# tunnelAmp.net
KiCad netlist of a schematic drawn in EAGLE
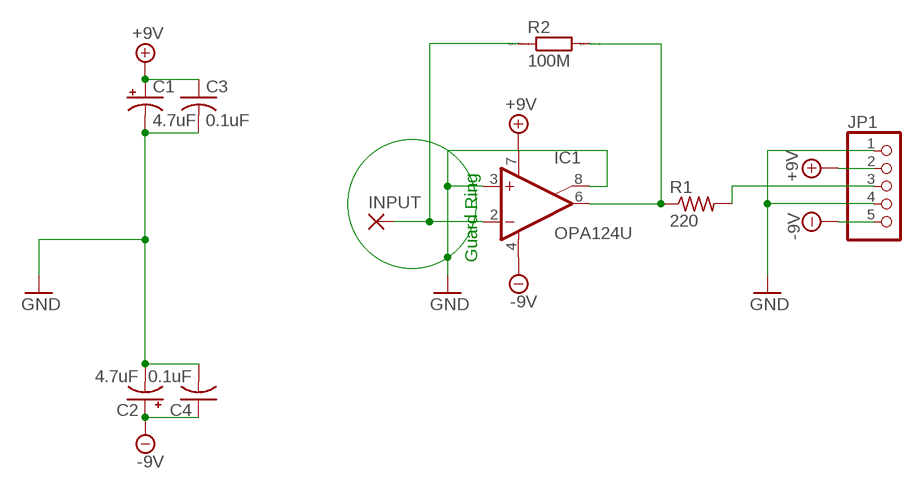
[diagram p0: schematic, sheet 1]

(export (version "E")
  (design (tool "Eeschema 10.0.6"))
  (components
    (comp (ref "C1")
      (value "4.7uF")
      (footprint "eagle-import:C_6032-28W")
      (libsource (lib "eagle-import") (part "CPOL-USC/6032-28W"))
    )
    (comp (ref "C2")
      (value "4.7uF")
      (footprint "eagle-import:C_6032-28W")
      (libsource (lib "eagle-import") (part "CPOL-USC/6032-28W"))
    )
    (comp (ref "C3")
      (value "0.1uF")
      (footprint "eagle-import:C0603")
      (libsource (lib "eagle-import") (part "C-USC0603"))
    )
    (comp (ref "C4")
      (value "0.1uF")
      (footprint "eagle-import:C0603")
      (libsource (lib "eagle-import") (part "C-USC0603"))
    )
    (comp (ref "IC1")
      (value "OPA124U")
      (footprint "eagle-import:SO08")
      (libsource (lib "eagle-import") (part "OPA124U"))
    )
    (comp (ref "INPUT")
      (value "2,54/1,1")
      (footprint "eagle-import:2,54_1,1")
      (libsource (lib "eagle-import") (part "2,54/1,1"))
    )
    (comp (ref "JP1")
      (value "PINHD-1X5")
      (footprint "eagle-import:1X05")
      (libsource (lib "eagle-import") (part "PINHD-1X5"))
    )
    (comp (ref "R1")
      (value "220")
      (footprint "eagle-import:R0603")
      (libsource (lib "eagle-import") (part "R-US_R0603"))
    )
    (comp (ref "R2")
      (value "100M")
      (footprint "eagle-import:R1206")
      (libsource (lib "eagle-import") (part "RR1206"))
    )
  )
  (nets
    (net (code "1") (name "+9V") (class "Default")
      (node (ref "C1") (pin "+") (pinfunction "+_+") (pintype "passive"))
      (node (ref "C3") (pin "1") (pinfunction "1_1") (pintype "passive"))
      (node (ref "IC1") (pin "7") (pinfunction "V+_7") (pintype "power_in"))
      (node (ref "JP1") (pin "2") (pinfunction "2_2") (pintype "passive"))
    )
    (net (code "2") (name "-9V") (class "Default")
      (node (ref "C2") (pin "+") (pinfunction "+_+") (pintype "passive"))
      (node (ref "C4") (pin "1") (pinfunction "1_1") (pintype "passive"))
      (node (ref "IC1") (pin "4") (pinfunction "V-_4") (pintype "power_in"))
      (node (ref "JP1") (pin "5") (pinfunction "5_5") (pintype "passive"))
    )
    (net (code "3") (name "GND") (class "Default")
      (node (ref "C1") (pin "-") (pinfunction "-_-") (pintype "passive"))
      (node (ref "C2") (pin "-") (pinfunction "-_-") (pintype "passive"))
      (node (ref "C3") (pin "2") (pinfunction "2_2") (pintype "passive"))
      (node (ref "C4") (pin "2") (pinfunction "2_2") (pintype "passive"))
      (node (ref "IC1") (pin "3") (pinfunction "+IN_3") (pintype "input"))
      (node (ref "IC1") (pin "8") (pinfunction "SUBS_8") (pintype "passive"))
      (node (ref "JP1") (pin "1") (pinfunction "1_1") (pintype "passive"))
      (node (ref "JP1") (pin "4") (pinfunction "4_4") (pintype "passive"))
    )
    (net (code "4") (name "Net-(IC1--IN)") (class "Default")
      (node (ref "IC1") (pin "2") (pinfunction "-IN_2") (pintype "input"))
      (node (ref "INPUT") (pin "1") (pinfunction "P_1") (pintype "passive"))
      (node (ref "R2") (pin "1") (pinfunction "1_1") (pintype "passive"))
    )
    (net (code "5") (name "Net-(IC1-OUT)") (class "Default")
      (node (ref "IC1") (pin "6") (pinfunction "OUT_6") (pintype "output"))
      (node (ref "R1") (pin "1") (pinfunction "1_1") (pintype "passive"))
      (node (ref "R2") (pin "2") (pinfunction "2_2") (pintype "passive"))
    )
    (net (code "6") (name "Net-(JP1-Pad3)") (class "Default")
      (node (ref "JP1") (pin "3") (pinfunction "3_3") (pintype "passive"))
      (node (ref "R1") (pin "2") (pinfunction "2_2") (pintype "passive"))
    )
  )
)
